# POL.net
KiCad netlist of a schematic drawn in Altium Designer
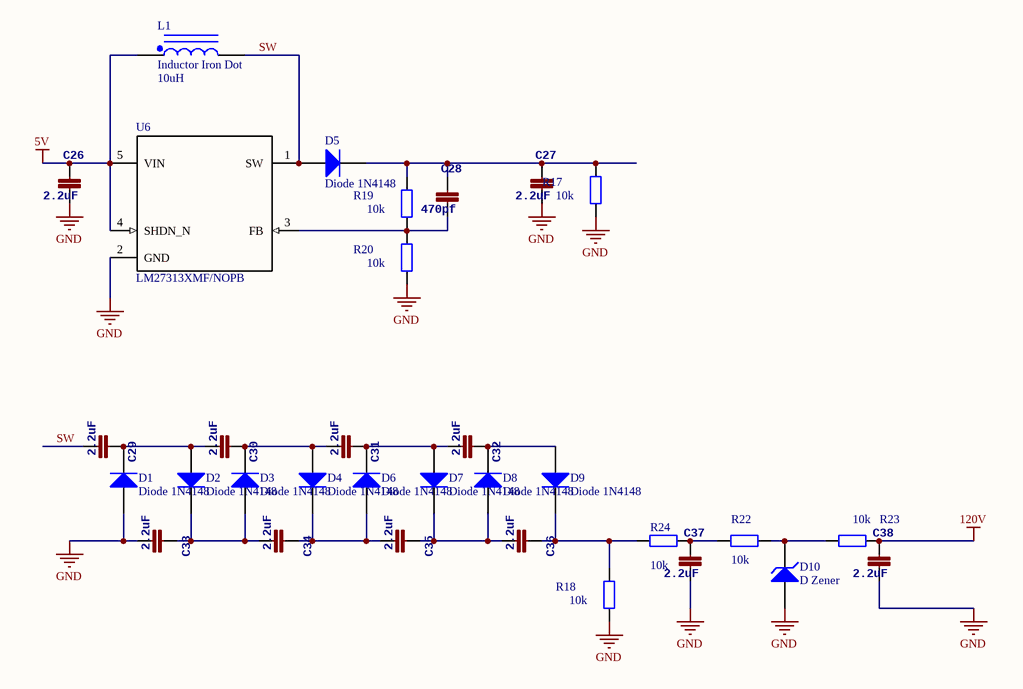
[diagram p0: POL.SchDoc]

(export (version "E")
  (design (tool "Eeschema 10.0.6"))
  (components
    (comp (ref "C26")
      (value "2.2uF")
      (footprint "0805")
      (description "<b>Capacitor</b>\nStandard 0603 ceramic capacitor, and 0.1\" leaded capacitor.")
      (fields (field (name "PARTNO") "CC0402ZRY5V7BB104"))
      (libsource (lib "pixhawk2") (part "CAP0402-CAP"))
    )
    (comp (ref "C27")
      (value "2.2uF")
      (footprint "0805")
      (description "<b>Capacitor</b>\nStandard 0603 ceramic capacitor, and 0.1\" leaded capacitor.")
      (fields (field (name "PARTNO") "CC0402ZRY5V7BB104"))
      (libsource (lib "pixhawk2") (part "CAP0402-CAP"))
    )
    (comp (ref "C28")
      (value "470pf")
      (footprint "0402")
      (description "<b>Capacitor</b>\nStandard 0603 ceramic capacitor, and 0.1\" leaded capacitor.")
      (fields (field (name "PARTNO") "CC0402ZRY5V7BB104"))
      (libsource (lib "pixhawk2") (part "CAP0402-CAP"))
    )
    (comp (ref "C29")
      (value "2.2uF")
      (footprint "0805")
      (description "<b>Capacitor</b>\nStandard 0603 ceramic capacitor, and 0.1\" leaded capacitor.")
      (fields (field (name "PARTNO") "CC0402ZRY5V7BB104"))
      (libsource (lib "") (part "CAP0402-CAP_1"))
    )
    (comp (ref "C30")
      (value "2.2uF")
      (footprint "0805")
      (description "<b>Capacitor</b>\nStandard 0603 ceramic capacitor, and 0.1\" leaded capacitor.")
      (fields (field (name "PARTNO") "CC0402ZRY5V7BB104"))
      (libsource (lib "") (part "CAP0402-CAP_1"))
    )
    (comp (ref "C31")
      (value "2.2uF")
      (footprint "0805")
      (description "<b>Capacitor</b>\nStandard 0603 ceramic capacitor, and 0.1\" leaded capacitor.")
      (fields (field (name "PARTNO") "CC0402ZRY5V7BB104"))
      (libsource (lib "") (part "CAP0402-CAP_1"))
    )
    (comp (ref "C32")
      (value "2.2uF")
      (footprint "0805")
      (description "<b>Capacitor</b>\nStandard 0603 ceramic capacitor, and 0.1\" leaded capacitor.")
      (fields (field (name "PARTNO") "CC0402ZRY5V7BB104"))
      (libsource (lib "") (part "CAP0402-CAP_1"))
    )
    (comp (ref "C33")
      (value "2.2uF")
      (footprint "0805")
      (description "<b>Capacitor</b>\nStandard 0603 ceramic capacitor, and 0.1\" leaded capacitor.")
      (fields (field (name "PARTNO") "CC0402ZRY5V7BB104"))
      (libsource (lib "") (part "CAP0402-CAP_1"))
    )
    (comp (ref "C34")
      (value "2.2uF")
      (footprint "0805")
      (description "<b>Capacitor</b>\nStandard 0603 ceramic capacitor, and 0.1\" leaded capacitor.")
      (fields (field (name "PARTNO") "CC0402ZRY5V7BB104"))
      (libsource (lib "") (part "CAP0402-CAP_1"))
    )
    (comp (ref "C35")
      (value "2.2uF")
      (footprint "0805")
      (description "<b>Capacitor</b>\nStandard 0603 ceramic capacitor, and 0.1\" leaded capacitor.")
      (fields (field (name "PARTNO") "CC0402ZRY5V7BB104"))
      (libsource (lib "") (part "CAP0402-CAP_1"))
    )
    (comp (ref "C36")
      (value "2.2uF")
      (footprint "0805")
      (description "<b>Capacitor</b>\nStandard 0603 ceramic capacitor, and 0.1\" leaded capacitor.")
      (fields (field (name "PARTNO") "CC0402ZRY5V7BB104"))
      (libsource (lib "") (part "CAP0402-CAP_1"))
    )
    (comp (ref "C37")
      (value "2.2uF")
      (footprint "0805")
      (description "<b>Capacitor</b>\nStandard 0603 ceramic capacitor, and 0.1\" leaded capacitor.")
      (fields (field (name "PARTNO") "CC0402ZRY5V7BB104"))
      (libsource (lib "pixhawk2") (part "CAP0402-CAP"))
    )
    (comp (ref "C38")
      (value "2.2uF")
      (footprint "0805")
      (description "<b>Capacitor</b>\nStandard 0603 ceramic capacitor, and 0.1\" leaded capacitor.")
      (fields (field (name "PARTNO") "CC0402ZRY5V7BB104"))
      (libsource (lib "pixhawk2") (part "CAP0402-CAP"))
    )
    (comp (ref "D1")
      (value "Diode 1N4148")
      (footprint "LC-SOD-323")
      (description "High Conductance Fast Diode")
      (fields (field (name "PUBLISHER") "Altium Limited"))
      (libsource (lib "Miscellaneous Devices") (part "Diode 1N4148"))
    )
    (comp (ref "D2")
      (value "Diode 1N4148")
      (footprint "LC-SOD-323")
      (description "High Conductance Fast Diode")
      (fields (field (name "PUBLISHER") "Altium Limited"))
      (libsource (lib "Miscellaneous Devices") (part "Diode 1N4148"))
    )
    (comp (ref "D3")
      (value "Diode 1N4148")
      (footprint "LC-SOD-323")
      (description "High Conductance Fast Diode")
      (fields (field (name "PUBLISHER") "Altium Limited"))
      (libsource (lib "Miscellaneous Devices") (part "Diode 1N4148"))
    )
    (comp (ref "D4")
      (value "Diode 1N4148")
      (footprint "LC-SOD-323")
      (description "High Conductance Fast Diode")
      (fields (field (name "PUBLISHER") "Altium Limited"))
      (libsource (lib "Miscellaneous Devices") (part "Diode 1N4148"))
    )
    (comp (ref "D5")
      (value "Diode 1N4148")
      (footprint "LC-SOD-323")
      (description "High Conductance Fast Diode")
      (fields (field (name "PUBLISHER") "Altium Limited"))
      (libsource (lib "Miscellaneous Devices") (part "Diode 1N4148"))
    )
    (comp (ref "D6")
      (value "Diode 1N4148")
      (footprint "LC-SOD-323")
      (description "High Conductance Fast Diode")
      (fields (field (name "PUBLISHER") "Altium Limited"))
      (libsource (lib "Miscellaneous Devices") (part "Diode 1N4148"))
    )
    (comp (ref "D7")
      (value "Diode 1N4148")
      (footprint "LC-SOD-323")
      (description "High Conductance Fast Diode")
      (fields (field (name "PUBLISHER") "Altium Limited"))
      (libsource (lib "Miscellaneous Devices") (part "Diode 1N4148"))
    )
    (comp (ref "D8")
      (value "Diode 1N4148")
      (footprint "LC-SOD-323")
      (description "High Conductance Fast Diode")
      (fields (field (name "PUBLISHER") "Altium Limited"))
      (libsource (lib "Miscellaneous Devices") (part "Diode 1N4148"))
    )
    (comp (ref "D9")
      (value "Diode 1N4148")
      (footprint "LC-SOD-323")
      (description "High Conductance Fast Diode")
      (fields (field (name "PUBLISHER") "Altium Limited"))
      (libsource (lib "Miscellaneous Devices") (part "Diode 1N4148"))
    )
    (comp (ref "D10")
      (value "D Zener")
      (footprint "LC-SOT-323(SC-70):SMA")
      (description "Zener Diode")
      (fields (field (name "PUBLISHER") "Altium Limited"))
      (libsource (lib "Miscellaneous Devices") (part "D Zener"))
    )
    (comp (ref "L1")
      (value "Inductor Iron Dot")
      (footprint "L4015")
      (description "Magnetic-Core Inductor with Winding Polarity Marking")
      (fields (field (name "ALTIUM_VALUE") "10uH") (field (name "PUBLISHER") "Altium Limited"))
      (libsource (lib "Miscellaneous Devices") (part "Inductor Iron Dot"))
    )
    (comp (ref "R17")
      (value "10k")
      (footprint "0402")
      (description "Resistor")
      (fields (field (name "PUBLISHER") "Altium Limited"))
      (libsource (lib "Miscellaneous Devices") (part "Res2"))
    )
    (comp (ref "R18")
      (value "10k")
      (footprint "0402")
      (description "Resistor")
      (fields (field (name "PUBLISHER") "Altium Limited"))
      (libsource (lib "Miscellaneous Devices") (part "Res2"))
    )
    (comp (ref "R19")
      (value "10k")
      (footprint "0402")
      (description "Resistor")
      (fields (field (name "PUBLISHER") "Altium Limited"))
      (libsource (lib "Miscellaneous Devices") (part "Res2"))
    )
    (comp (ref "R20")
      (value "10k")
      (footprint "0402")
      (description "Resistor")
      (fields (field (name "PUBLISHER") "Altium Limited"))
      (libsource (lib "Miscellaneous Devices") (part "Res2"))
    )
    (comp (ref "R22")
      (value "10k")
      (footprint "0402")
      (description "Resistor")
      (fields (field (name "PUBLISHER") "Altium Limited"))
      (libsource (lib "") (part "Res2_1"))
    )
    (comp (ref "R23")
      (value "10k")
      (footprint "0402")
      (description "Resistor")
      (fields (field (name "PUBLISHER") "Altium Limited"))
      (libsource (lib "") (part "Res2_1"))
    )
    (comp (ref "R24")
      (value "10k")
      (footprint "0402")
      (description "Resistor")
      (fields (field (name "PUBLISHER") "Altium Limited"))
      (libsource (lib "") (part "Res2_1"))
    )
    (comp (ref "U6")
      (value "LM27313XMF/NOPB")
      (footprint "SOT23-5")
      (description "Imported")
      (fields (field (name "MANUFACTURER") "Texas Instruments"))
      (libsource (lib "complements") (part "LM27313XMF/NOPB"))
    )
  )
  (nets
    (net (code "1") (name "/SW") (class "Default")
      (node (ref "C29") (pin "1") (pinfunction "1_1") (pintype "passive"))
      (node (ref "D5") (pin "1") (pinfunction "A_1") (pintype "passive"))
      (node (ref "L1") (pin "2") (pinfunction "2_2") (pintype "passive"))
      (node (ref "U6") (pin "1") (pinfunction "SW_1") (pintype "power_in"))
    )
    (net (code "2") (name "5V") (class "Default")
      (node (ref "C26") (pin "2") (pinfunction "2_2") (pintype "passive"))
      (node (ref "L1") (pin "1") (pinfunction "1_1") (pintype "passive"))
      (node (ref "U6") (pin "4") (pinfunction "SHDN_N_4") (pintype "input"))
      (node (ref "U6") (pin "5") (pinfunction "VIN_5") (pintype "power_in"))
    )
    (net (code "3") (name "120V") (class "Default")
      (node (ref "C38") (pin "2") (pinfunction "2_2") (pintype "passive"))
      (node (ref "R23") (pin "1") (pinfunction "1_1") (pintype "passive"))
    )
    (net (code "4") (name "GND") (class "Default")
      (node (ref "C26") (pin "1") (pinfunction "1_1") (pintype "passive"))
      (node (ref "C27") (pin "1") (pinfunction "1_1") (pintype "passive"))
      (node (ref "C33") (pin "1") (pinfunction "1_1") (pintype "passive"))
      (node (ref "C37") (pin "1") (pinfunction "1_1") (pintype "passive"))
      (node (ref "C38") (pin "1") (pinfunction "1_1") (pintype "passive"))
      (node (ref "D1") (pin "1") (pinfunction "A_1") (pintype "passive"))
      (node (ref "D10") (pin "1") (pinfunction "A_1") (pintype "passive"))
      (node (ref "R17") (pin "1") (pinfunction "1_1") (pintype "passive"))
      (node (ref "R18") (pin "1") (pinfunction "1_1") (pintype "passive"))
      (node (ref "R20") (pin "1") (pinfunction "1_1") (pintype "passive"))
      (node (ref "U6") (pin "2") (pinfunction "GND_2") (pintype "power_in"))
    )
    (net (code "5") (name "Net-(C37-Pad2)") (class "Default")
      (node (ref "C37") (pin "2") (pinfunction "2_2") (pintype "passive"))
      (node (ref "R22") (pin "2") (pinfunction "2_2") (pintype "passive"))
      (node (ref "R24") (pin "1") (pinfunction "1_1") (pintype "passive"))
    )
    (net (code "6") (name "Net-(D1-K)") (class "Default")
      (node (ref "C29") (pin "2") (pinfunction "2_2") (pintype "passive"))
      (node (ref "C30") (pin "1") (pinfunction "1_1") (pintype "passive"))
      (node (ref "D1") (pin "2") (pinfunction "K_2") (pintype "passive"))
      (node (ref "D2") (pin "1") (pinfunction "A_1") (pintype "passive"))
    )
    (net (code "7") (name "Net-(D2-K)") (class "Default")
      (node (ref "C33") (pin "2") (pinfunction "2_2") (pintype "passive"))
      (node (ref "C34") (pin "1") (pinfunction "1_1") (pintype "passive"))
      (node (ref "D2") (pin "2") (pinfunction "K_2") (pintype "passive"))
      (node (ref "D3") (pin "1") (pinfunction "A_1") (pintype "passive"))
    )
    (net (code "8") (name "Net-(D3-K)") (class "Default")
      (node (ref "C30") (pin "2") (pinfunction "2_2") (pintype "passive"))
      (node (ref "C31") (pin "1") (pinfunction "1_1") (pintype "passive"))
      (node (ref "D3") (pin "2") (pinfunction "K_2") (pintype "passive"))
      (node (ref "D4") (pin "1") (pinfunction "A_1") (pintype "passive"))
    )
    (net (code "9") (name "Net-(D4-K)") (class "Default")
      (node (ref "C34") (pin "2") (pinfunction "2_2") (pintype "passive"))
      (node (ref "C35") (pin "1") (pinfunction "1_1") (pintype "passive"))
      (node (ref "D4") (pin "2") (pinfunction "K_2") (pintype "passive"))
      (node (ref "D6") (pin "1") (pinfunction "A_1") (pintype "passive"))
    )
    (net (code "10") (name "Net-(D5-K)") (class "Default")
      (node (ref "C27") (pin "2") (pinfunction "2_2") (pintype "passive"))
      (node (ref "C28") (pin "2") (pinfunction "2_2") (pintype "passive"))
      (node (ref "D5") (pin "2") (pinfunction "K_2") (pintype "passive"))
      (node (ref "R17") (pin "2") (pinfunction "2_2") (pintype "passive"))
      (node (ref "R19") (pin "2") (pinfunction "2_2") (pintype "passive"))
    )
    (net (code "11") (name "Net-(D6-K)") (class "Default")
      (node (ref "C31") (pin "2") (pinfunction "2_2") (pintype "passive"))
      (node (ref "C32") (pin "1") (pinfunction "1_1") (pintype "passive"))
      (node (ref "D6") (pin "2") (pinfunction "K_2") (pintype "passive"))
      (node (ref "D7") (pin "1") (pinfunction "A_1") (pintype "passive"))
    )
    (net (code "12") (name "Net-(D7-K)") (class "Default")
      (node (ref "C35") (pin "2") (pinfunction "2_2") (pintype "passive"))
      (node (ref "C36") (pin "1") (pinfunction "1_1") (pintype "passive"))
      (node (ref "D7") (pin "2") (pinfunction "K_2") (pintype "passive"))
      (node (ref "D8") (pin "1") (pinfunction "A_1") (pintype "passive"))
    )
    (net (code "13") (name "Net-(D8-K)") (class "Default")
      (node (ref "C32") (pin "2") (pinfunction "2_2") (pintype "passive"))
      (node (ref "D8") (pin "2") (pinfunction "K_2") (pintype "passive"))
      (node (ref "D9") (pin "1") (pinfunction "A_1") (pintype "passive"))
    )
    (net (code "14") (name "Net-(D9-K)") (class "Default")
      (node (ref "C36") (pin "2") (pinfunction "2_2") (pintype "passive"))
      (node (ref "D9") (pin "2") (pinfunction "K_2") (pintype "passive"))
      (node (ref "R18") (pin "2") (pinfunction "2_2") (pintype "passive"))
      (node (ref "R24") (pin "2") (pinfunction "2_2") (pintype "passive"))
    )
    (net (code "15") (name "Net-(D10-K)") (class "Default")
      (node (ref "D10") (pin "2") (pinfunction "K_2") (pintype "passive"))
      (node (ref "R22") (pin "1") (pinfunction "1_1") (pintype "passive"))
      (node (ref "R23") (pin "2") (pinfunction "2_2") (pintype "passive"))
    )
    (net (code "16") (name "Net-(U6-FB)") (class "Default")
      (node (ref "C28") (pin "1") (pinfunction "1_1") (pintype "passive"))
      (node (ref "R19") (pin "1") (pinfunction "1_1") (pintype "passive"))
      (node (ref "R20") (pin "2") (pinfunction "2_2") (pintype "passive"))
      (node (ref "U6") (pin "3") (pinfunction "FB_3") (pintype "input"))
    )
  )
)
